# TX.net
KiCad netlist of a schematic drawn in Altium Designer
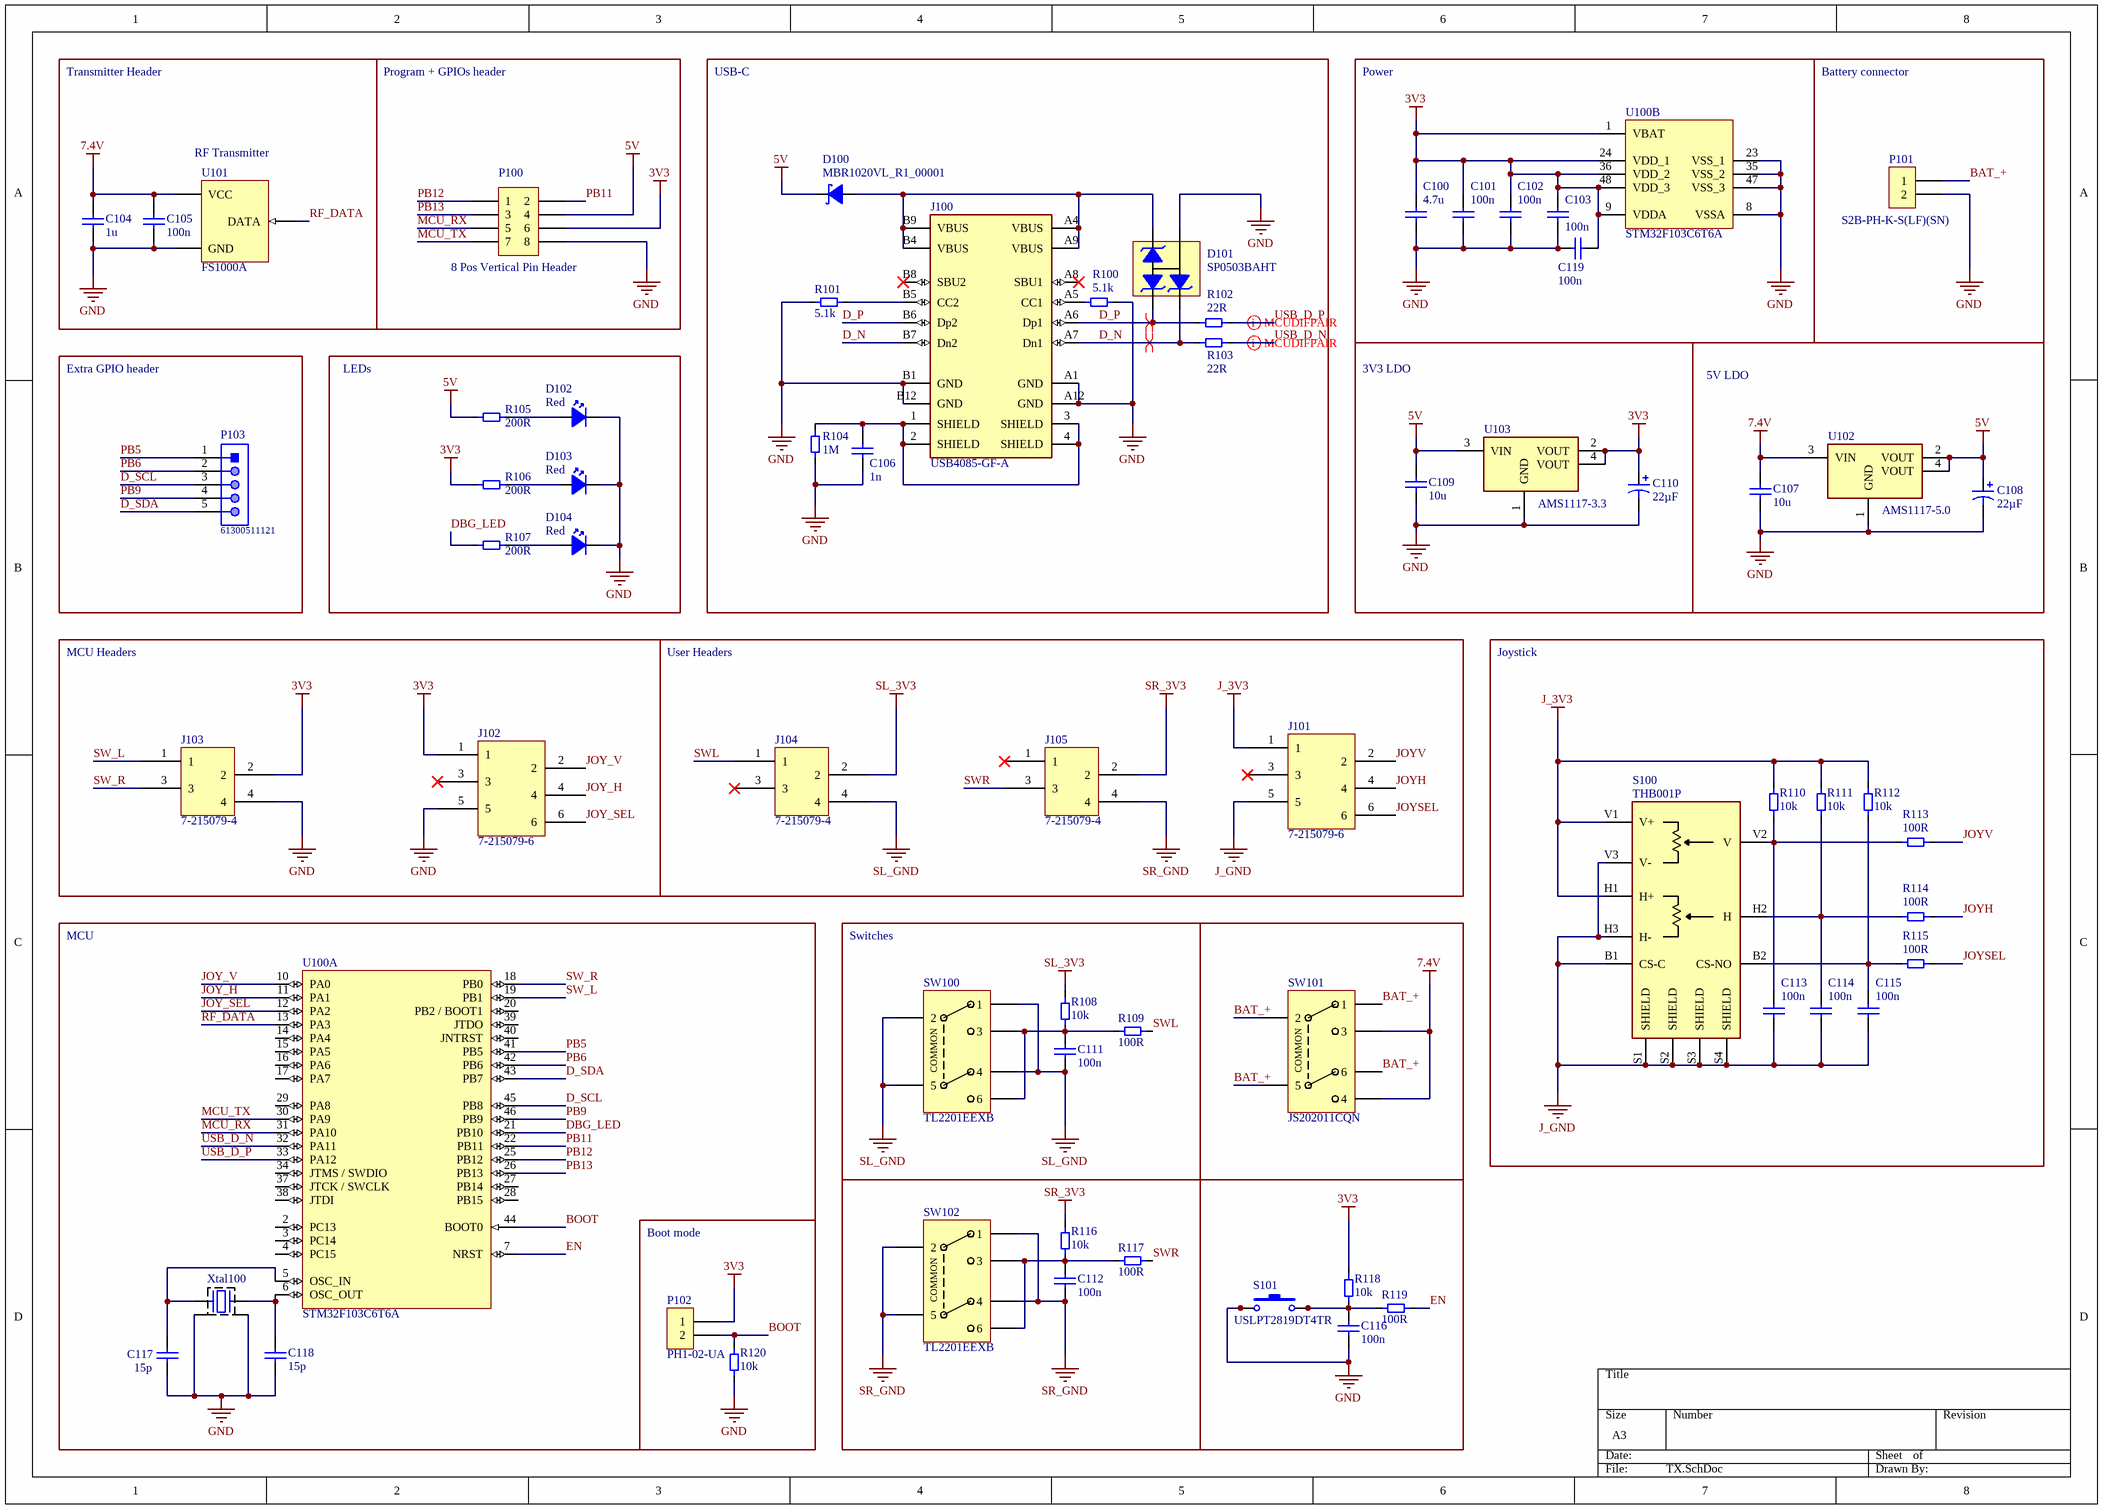
[diagram p0: TX.SchDoc]

(export (version "E")
  (design (tool "Eeschema 10.0.6"))
  (components
    (comp (ref "C100")
      (value "4.7u")
      (footprint "MLCC_0805_M")
      (description "MLCC, 0805, 4.7u, 20%, 50V, X5R")
      (fields (field (name "MANUFACTURER") "Any") (field (name "VOLTAGE") "50V"))
      (libsource (lib "Krakul Vault") (part "CAPACITOR_NONPOL_IEC"))
    )
    (comp (ref "C101")
      (value "100n")
      (footprint "MLCC_0603_M")
      (description "MLCC, 0603, 100n, 10%, 50V, X7R")
      (fields (field (name "VOLTAGE") "50V") (field (name "TOLERANCE") "10%"))
      (libsource (lib "Krakul Vault") (part "CAPACITOR_NONPOL_IEC"))
    )
    (comp (ref "C102")
      (value "100n")
      (footprint "MLCC_0603_M")
      (description "MLCC, 0603, 100n, 10%, 50V, X7R")
      (fields (field (name "VOLTAGE") "50V") (field (name "TOLERANCE") "10%"))
      (libsource (lib "Krakul Vault") (part "CAPACITOR_NONPOL_IEC"))
    )
    (comp (ref "C103")
      (value "100n")
      (footprint "MLCC_0603_M")
      (description "MLCC, 0603, 100n, 10%, 50V, X7R")
      (fields (field (name "VOLTAGE") "50V") (field (name "TOLERANCE") "10%"))
      (libsource (lib "Krakul Vault") (part "CAPACITOR_NONPOL_IEC"))
    )
    (comp (ref "C104")
      (value "1u")
      (footprint "MLCC_0603_M")
      (description "MLCC, 0603, 1u, 10%, 50V, X5R")
      (fields (field (name "MANUFACTURER") "Any") (field (name "VOLTAGE") "50V"))
      (libsource (lib "Krakul Vault") (part "CAPACITOR_NONPOL_IEC"))
    )
    (comp (ref "C105")
      (value "100n")
      (footprint "MLCC_0603_M")
      (description "MLCC, 0603, 100n, 10%, 50V, X7R")
      (fields (field (name "VOLTAGE") "50V") (field (name "TOLERANCE") "10%"))
      (libsource (lib "Krakul Vault") (part "CAPACITOR_NONPOL_IEC"))
    )
    (comp (ref "C106")
      (value "1n")
      (footprint "MLCC_0603_M")
      (description "MLCC, 0603, 1n, 10%, 50V, X7R")
      (fields (field (name "MANUFACTURER") "Any") (field (name "VOLTAGE") "50V"))
      (libsource (lib "Krakul Vault") (part "CAPACITOR_NONPOL_IEC"))
    )
    (comp (ref "C107")
      (value "10u")
      (footprint "MLCC_0805_M")
      (description "MLCC, 0805, 10u, 10%, 50V, X5R")
      (fields (field (name "TOLERANCE") "10%") (field (name "VOLTAGE") "50V"))
      (libsource (lib "Krakul Vault") (part "CAPACITOR_NONPOL_IEC"))
    )
    (comp (ref "C108")
      (value "22µF")
      (footprint "1210_Tantalum")
      (description "Cap Tant Solid 22uF 25V B CASE 20% (3.5 X 2.8 X 1.9mm) SMD 3528-21 0.15 Ohm 105°C T/R")
      (fields (field (name "TOLERANCE") "20%") (field (name "MANUFACTURER") "AVX Corporation"))
      (libsource (lib "Krakul Vault") (part "GENERIC TANT CAP"))
    )
    (comp (ref "C109")
      (value "10u")
      (footprint "MLCC_0805_M")
      (description "MLCC, 0805, 10u, 10%, 50V, X5R")
      (fields (field (name "TOLERANCE") "10%") (field (name "VOLTAGE") "50V"))
      (libsource (lib "Krakul Vault") (part "CAPACITOR_NONPOL_IEC"))
    )
    (comp (ref "C110")
      (value "22µF")
      (footprint "1210_Tantalum")
      (description "Cap Tant Solid 22uF 25V B CASE 20% (3.5 X 2.8 X 1.9mm) SMD 3528-21 0.15 Ohm 105°C T/R")
      (fields (field (name "TOLERANCE") "20%") (field (name "MANUFACTURER") "AVX Corporation"))
      (libsource (lib "Krakul Vault") (part "GENERIC TANT CAP"))
    )
    (comp (ref "C111")
      (value "100n")
      (footprint "MLCC_0603_M")
      (description "MLCC, 0603, 100n, 10%, 50V, X7R")
      (fields (field (name "VOLTAGE") "50V") (field (name "TOLERANCE") "10%"))
      (libsource (lib "Krakul Vault") (part "CAPACITOR_NONPOL_IEC"))
    )
    (comp (ref "C112")
      (value "100n")
      (footprint "MLCC_0603_M")
      (description "MLCC, 0603, 100n, 10%, 50V, X7R")
      (fields (field (name "VOLTAGE") "50V") (field (name "TOLERANCE") "10%"))
      (libsource (lib "Krakul Vault") (part "CAPACITOR_NONPOL_IEC"))
    )
    (comp (ref "C113")
      (value "100n")
      (footprint "MLCC_0603_M")
      (description "MLCC, 0603, 100n, 10%, 50V, X7R")
      (fields (field (name "VOLTAGE") "50V") (field (name "TOLERANCE") "10%"))
      (libsource (lib "Krakul Vault") (part "CAPACITOR_NONPOL_IEC"))
    )
    (comp (ref "C114")
      (value "100n")
      (footprint "MLCC_0603_M")
      (description "MLCC, 0603, 100n, 10%, 50V, X7R")
      (fields (field (name "VOLTAGE") "50V") (field (name "TOLERANCE") "10%"))
      (libsource (lib "Krakul Vault") (part "CAPACITOR_NONPOL_IEC"))
    )
    (comp (ref "C115")
      (value "100n")
      (footprint "MLCC_0603_M")
      (description "MLCC, 0603, 100n, 10%, 50V, X7R")
      (fields (field (name "VOLTAGE") "50V") (field (name "TOLERANCE") "10%"))
      (libsource (lib "Krakul Vault") (part "CAPACITOR_NONPOL_IEC"))
    )
    (comp (ref "C116")
      (value "100n")
      (footprint "MLCC_0603_M")
      (description "MLCC, 0603, 100n, 10%, 50V, X7R")
      (fields (field (name "VOLTAGE") "50V") (field (name "TOLERANCE") "10%"))
      (libsource (lib "Krakul Vault") (part "CAPACITOR_NONPOL_IEC"))
    )
    (comp (ref "C117")
      (value "15p")
      (footprint "MLCC_0402_M")
      (description "MLCC, 0402, 15p, 10%, 25V, C0G/NP0")
      (fields (field (name "MANUFACTURER") "Any") (field (name "TOLERANCE") "10%"))
      (libsource (lib "Krakul Vault") (part "CAPACITOR_NONPOL_IEC"))
    )
    (comp (ref "C118")
      (value "15p")
      (footprint "MLCC_0402_M")
      (description "MLCC, 0402, 15p, 10%, 25V, C0G/NP0")
      (fields (field (name "MANUFACTURER") "Any") (field (name "TOLERANCE") "10%"))
      (libsource (lib "Krakul Vault") (part "CAPACITOR_NONPOL_IEC"))
    )
    (comp (ref "C119")
      (value "100n")
      (footprint "MLCC_0603_M")
      (description "MLCC, 0603, 100n, 10%, 50V, X7R")
      (fields (field (name "VOLTAGE") "50V") (field (name "TOLERANCE") "10%"))
      (libsource (lib "Krakul Vault") (part "CAPACITOR_NONPOL_IEC"))
    )
    (comp (ref "D100")
      (value "MBR1020VL_R1_00001")
      (footprint "FP-MBR1020VL_R1_00001-MFG")
      (description "Rectifier Diode, Schottky, 1 Phase, 1 Element, 1A, 20V V(RRM), Silicon")
      (fields (field (name "MANUFACTURER") "Panjit"))
      (libsource (lib "Krakul Vault") (part "Schottky generic 2 pins"))
    )
    (comp (ref "D101")
      (value "SP0503BAHT")
      (footprint "LFUS-SOT143-4_V")
      (description "SP050xBA Series 8.5 V 30 pF Triple Uni-Directional TVS Avalanche Diode-SOT143-4")
      (fields (field (name "MANUFACTURER") "Littelfuse Inc."))
      (libsource (lib "Krakul Vault") (part "SOT-143"))
    )
    (comp (ref "D102")
      (value "Red")
      (footprint "0603 RED LED")
      (description "Generic red 0603 LED")
      (fields (field (name "PART NUMBER") "Any Red 0603 LED") (field (name "MANUFACTURER") "Any"))
      (libsource (lib "Krakul Vault") (part "LED generic"))
    )
    (comp (ref "D103")
      (value "Red")
      (footprint "0603 RED LED")
      (description "Generic red 0603 LED")
      (fields (field (name "PART NUMBER") "Any Red 0603 LED") (field (name "MANUFACTURER") "Any"))
      (libsource (lib "Krakul Vault") (part "LED generic"))
    )
    (comp (ref "D104")
      (value "Red")
      (footprint "0603 RED LED")
      (description "Generic red 0603 LED")
      (fields (field (name "PART NUMBER") "Any Red 0603 LED") (field (name "MANUFACTURER") "Any"))
      (libsource (lib "Krakul Vault") (part "LED generic"))
    )
    (comp (ref "J100")
      (value "USB4085-GF-A")
      (footprint "FP-USB4085-GF-A-MFG")
      (description "USB Connector, 16 Contact(s), Female, Right Angle, Solder Terminal, Locking, Receptacle")
      (fields (field (name "MANUFACTURER") "GCT") (field (name "PART NUMBER") "USB4800-03-A"))
      (libsource (lib "Krakul Vault") (part "USB4085-GF-A"))
    )
    (comp (ref "J101")
      (value "7-215079-6")
      (footprint "7-215079-6-Footprint-1")
      (description "Conn FFC Connector F 6 POS 1.27mm Solder ST Thru-Hole Automotive Box/Carton")
      (fields (field (name "MANUFACTURER") "TE Connectivity"))
      (libsource (lib "Krakul Vault") (part "7-215079-6"))
    )
    (comp (ref "J102")
      (value "7-215079-6")
      (footprint "7-215079-6-Footprint-1")
      (description "Conn FFC Connector F 6 POS 1.27mm Solder ST Thru-Hole Automotive Box/Carton")
      (fields (field (name "MANUFACTURER") "TE Connectivity"))
      (libsource (lib "Krakul Vault") (part "7-215079-6"))
    )
    (comp (ref "J103")
      (value "7-215079-4")
      (footprint "7-215079-4")
      (description "Conn FFC Connector F 4 POS 1.27mm Solder ST Thru-Hole Box/Carton")
      (fields (field (name "MANUFACTURER") "TE connectivity") (field (name "PART NUMBER") "7-215079-6"))
      (libsource (lib "Krakul Vault") (part "7-215079-4"))
    )
    (comp (ref "J104")
      (value "7-215079-4")
      (footprint "7-215079-4")
      (description "Conn FFC Connector F 4 POS 1.27mm Solder ST Thru-Hole Box/Carton")
      (fields (field (name "MANUFACTURER") "TE connectivity") (field (name "PART NUMBER") "7-215079-6"))
      (libsource (lib "Krakul Vault") (part "7-215079-4"))
    )
    (comp (ref "J105")
      (value "7-215079-4")
      (footprint "7-215079-4")
      (description "Conn FFC Connector F 4 POS 1.27mm Solder ST Thru-Hole Box/Carton")
      (fields (field (name "MANUFACTURER") "TE connectivity") (field (name "PART NUMBER") "7-215079-6"))
      (libsource (lib "Krakul Vault") (part "7-215079-4"))
    )
    (comp (ref "P100")
      (value "8 Pos Vertical Pin Header")
      (footprint "8 POS Vertical Pin Header")
      (description "Connector Header Through Hole 8 position 0.100\" (2.54mm)")
      (fields (field (name "MANUFACTURER") "Amphenol ICC (FCI)") (field (name "PART NUMBER") "67997-208HLF"))
      (libsource (lib "Krakul Vault") (part "8POS GENERIC 2-LINE"))
    )
    (comp (ref "P101")
      (value "S2B-PH-K-S(LF)(SN)")
      (footprint "B5B-PH-K-S(LF)(SN)")
      (description "Conn Shrouded Header (4 Sides) HDR 2 POS 2mm Solder RA Thru-Hole Box")
      (fields (field (name "MANUFACTURER") "JST Sales America Inc."))
      (libsource (lib "Krakul Vault") (part "2POS GENERIC"))
    )
    (comp (ref "P102")
      (value "PH1-02-UA")
      (footprint "2Pos Pin Header Vertical")
      (description "Conn Unshrouded Header HDR 2 POS 2.54mm Solder ST Top Entry Thru-Hole Bag")
      (fields (field (name "PART NUMBER") "PH1-04-UA") (field (name "MANUFACTURER") "Adam Tech"))
      (libsource (lib "Krakul Vault") (part "2POS GENERIC"))
    )
    (comp (ref "P103")
      (value "61300511121")
      (footprint "61300511121")
      (description "Conn Unshrouded Header HDR 5 POS 2.54mm Solder ST Top Entry Thru-Hole Bag")
      (fields (field (name "MANUFACTURER") "Wurth"))
      (libsource (lib "Krakul Vault") (part "WE-CN-1P-M-R5"))
    )
    (comp (ref "R100")
      (value "5.1k")
      (footprint "Resistor_0603_M")
      (description "Resistor, 0603, 5.1k, 1%, 1/10W")
      (fields (field (name "POWER") "100mW") (field (name "MANUFACTURER") "Any"))
      (libsource (lib "Krakul Vault") (part "RESISTOR_GENERIC_IEC"))
    )
    (comp (ref "R101")
      (value "5.1k")
      (footprint "Resistor_0603_M")
      (description "Resistor, 0603, 5.1k, 1%, 1/10W")
      (fields (field (name "POWER") "100mW") (field (name "MANUFACTURER") "Any"))
      (libsource (lib "Krakul Vault") (part "RESISTOR_GENERIC_IEC"))
    )
    (comp (ref "R102")
      (value "22R")
      (footprint "Resistor_0603_M")
      (description "Resistor, 0603, 22R, 1%, 1/10W")
      (fields (field (name "TOLERANCE") "1%") (field (name "MANUFACTURER") "Any"))
      (libsource (lib "Krakul Vault") (part "RESISTOR_GENERIC_IEC"))
    )
    (comp (ref "R103")
      (value "22R")
      (footprint "Resistor_0603_M")
      (description "Resistor, 0603, 22R, 1%, 1/10W")
      (fields (field (name "TOLERANCE") "1%") (field (name "MANUFACTURER") "Any"))
      (libsource (lib "Krakul Vault") (part "RESISTOR_GENERIC_IEC"))
    )
    (comp (ref "R104")
      (value "1M")
      (footprint "Resistor_1206_M")
      (description "Resistor, 1206, 1M, 1%, 1/4W")
      (fields (field (name "MANUFACTURER") "Any"))
      (libsource (lib "Krakul Vault") (part "RESISTOR_GENERIC_IEC"))
    )
    (comp (ref "R105")
      (value "200R")
      (footprint "Resistor_0603_M")
      (description "Resistor, 0603, 200R, 1%, 1/10W")
      (fields (field (name "TOLERANCE") "1%") (field (name "POWER") "100mW"))
      (libsource (lib "Krakul Vault") (part "RESISTOR_GENERIC_IEC"))
    )
    (comp (ref "R106")
      (value "200R")
      (footprint "Resistor_0603_M")
      (description "Resistor, 0603, 200R, 1%, 1/10W")
      (fields (field (name "TOLERANCE") "1%") (field (name "POWER") "100mW"))
      (libsource (lib "Krakul Vault") (part "RESISTOR_GENERIC_IEC"))
    )
    (comp (ref "R107")
      (value "200R")
      (footprint "Resistor_0603_M")
      (description "Resistor, 0603, 200R, 1%, 1/10W")
      (fields (field (name "TOLERANCE") "1%") (field (name "POWER") "100mW"))
      (libsource (lib "Krakul Vault") (part "RESISTOR_GENERIC_IEC"))
    )
    (comp (ref "R108")
      (value "10k")
      (footprint "Resistor_0603_M")
      (description "Resistor, 0603, 10k, 1%, 1/10W")
      (fields (field (name "MANUFACTURER") "Any") (field (name "TOLERANCE") "1%"))
      (libsource (lib "Krakul Vault") (part "RESISTOR_GENERIC_IEC"))
    )
    (comp (ref "R109")
      (value "100R")
      (footprint "Resistor_0603_M")
      (description "Resistor, 0603, 100R, 1%, 1/10W")
      (fields (field (name "POWER") "100mW") (field (name "MANUFACTURER") "Any"))
      (libsource (lib "Krakul Vault") (part "RESISTOR_GENERIC_IEC"))
    )
    (comp (ref "R110")
      (value "10k")
      (footprint "Resistor_0603_M")
      (description "Resistor, 0603, 10k, 1%, 1/10W")
      (fields (field (name "MANUFACTURER") "Any") (field (name "TOLERANCE") "1%"))
      (libsource (lib "Krakul Vault") (part "RESISTOR_GENERIC_IEC"))
    )
    (comp (ref "R111")
      (value "10k")
      (footprint "Resistor_0603_M")
      (description "Resistor, 0603, 10k, 1%, 1/10W")
      (fields (field (name "MANUFACTURER") "Any") (field (name "TOLERANCE") "1%"))
      (libsource (lib "Krakul Vault") (part "RESISTOR_GENERIC_IEC"))
    )
    (comp (ref "R112")
      (value "10k")
      (footprint "Resistor_0603_M")
      (description "Resistor, 0603, 10k, 1%, 1/10W")
      (fields (field (name "MANUFACTURER") "Any") (field (name "TOLERANCE") "1%"))
      (libsource (lib "Krakul Vault") (part "RESISTOR_GENERIC_IEC"))
    )
    (comp (ref "R113")
      (value "100R")
      (footprint "Resistor_0603_M")
      (description "Resistor, 0603, 100R, 1%, 1/10W")
      (fields (field (name "POWER") "100mW") (field (name "MANUFACTURER") "Any"))
      (libsource (lib "Krakul Vault") (part "RESISTOR_GENERIC_IEC"))
    )
    (comp (ref "R114")
      (value "100R")
      (footprint "Resistor_0603_M")
      (description "Resistor, 0603, 100R, 1%, 1/10W")
      (fields (field (name "POWER") "100mW") (field (name "MANUFACTURER") "Any"))
      (libsource (lib "Krakul Vault") (part "RESISTOR_GENERIC_IEC"))
    )
    (comp (ref "R115")
      (value "100R")
      (footprint "Resistor_0603_M")
      (description "Resistor, 0603, 100R, 1%, 1/10W")
      (fields (field (name "POWER") "100mW") (field (name "MANUFACTURER") "Any"))
      (libsource (lib "Krakul Vault") (part "RESISTOR_GENERIC_IEC"))
    )
    (comp (ref "R116")
      (value "10k")
      (footprint "Resistor_0603_M")
      (description "Resistor, 0603, 10k, 1%, 1/10W")
      (fields (field (name "MANUFACTURER") "Any") (field (name "TOLERANCE") "1%"))
      (libsource (lib "Krakul Vault") (part "RESISTOR_GENERIC_IEC"))
    )
    (comp (ref "R117")
      (value "100R")
      (footprint "Resistor_0603_M")
      (description "Resistor, 0603, 100R, 1%, 1/10W")
      (fields (field (name "POWER") "100mW") (field (name "MANUFACTURER") "Any"))
      (libsource (lib "Krakul Vault") (part "RESISTOR_GENERIC_IEC"))
    )
    (comp (ref "R118")
      (value "10k")
      (footprint "Resistor_0603_M")
      (description "Resistor, 0603, 10k, 1%, 1/10W")
      (fields (field (name "MANUFACTURER") "Any") (field (name "TOLERANCE") "1%"))
      (libsource (lib "Krakul Vault") (part "RESISTOR_GENERIC_IEC"))
    )
    (comp (ref "R119")
      (value "100R")
      (footprint "Resistor_0603_M")
      (description "Resistor, 0603, 100R, 1%, 1/10W")
      (fields (field (name "POWER") "100mW") (field (name "MANUFACTURER") "Any"))
      (libsource (lib "Krakul Vault") (part "RESISTOR_GENERIC_IEC"))
    )
    (comp (ref "R120")
      (value "10k")
      (footprint "Resistor_0603_M")
      (description "Resistor, 0603, 10k, ≤5%, ≥1/16W")
      (fields (field (name "MANUFACTURER") "Any"))
      (libsource (lib "Krakul Vault") (part "RESISTOR_GENERIC_IEC"))
    )
    (comp (ref "S100")
      (value "THB001P")
      (footprint "THB001P")
      (description "Multi-Directional Thumbstick, 2 Axis, Center Momentary Switch, 12VDC, THB Series")
      (fields (field (name "MANUFACTURER") "Littelfuse"))
      (libsource (lib "Krakul Vault") (part "THB001P"))
    )
    (comp (ref "S101")
      (value "USLPT2819DT4TR")
      (footprint "USLPT2819DT4TR-Footprint-1")
      (description "Keypad Switch, SPST, 0.05A, 1.96N, Solder Terminal, Panel Mount")
      (fields (field (name "MANUFACTURER") "TE Connectivity ALCOSWITCH Switches"))
      (libsource (lib "Krakul Vault") (part "Copy of Switch 4-pin"))
    )
    (comp (ref "SW100")
      (value "TL2201EEXB")
      (footprint "TL2201EEXB-Footprint-1")
      (description "Pushbutton Switch, DPDT, ON-ON, 100 mA, 30V DC, PC Pin, TL2201 Series")
      (fields (field (name "MANUFACTURER") "E-Switch"))
      (libsource (lib "Krakul Vault") (part "TL2201EEXB-Symbol-1"))
    )
    (comp (ref "SW101")
      (value "JS202011CQN")
      (footprint "FP-JS202011CQN-MFG")
      (description "Slide Switch, 1 Positions, Dpdt, Latched, 0.3A, 6Vdc, 6 Pcb Hole Cnt, Solder Terminal, Through")
      (fields (field (name "MANUFACTURER") "C&K"))
      (libsource (lib "Krakul Vault") (part "JS202011CQN-Symbol-1"))
    )
    (comp (ref "SW102")
      (value "TL2201EEXB")
      (footprint "TL2201EEXB-Footprint-1")
      (description "Pushbutton Switch, DPDT, ON-ON, 100 mA, 30V DC, PC Pin, TL2201 Series")
      (fields (field (name "MANUFACTURER") "E-Switch"))
      (libsource (lib "Krakul Vault") (part "TL2201EEXB-Symbol-1"))
    )
    (comp (ref "U100")
      (value "STM32F103C6T6A")
      (footprint "STM-LQFP48_M")
      (description "MCU 32-bit STM32F ARM Cortex M3 RISC 32KB Flash 2.5V/3.3V 48-Pin LQFP Tray")
      (fields (field (name "MANUFACTURER") "STMicroelectronics") (field (name "PART NUMBER") "STM32F103C8T6"))
      (libsource (lib "Krakul Vault") (part "MC-ARM-STM32F103X4_6-SQ48"))
    )
    (comp (ref "U101")
      (value "FS1000A")
      (footprint "2.54mm 3-pin horizontal")
      (description "FS1000A 433MHZ RF transmitter & XY-MK-5V Receiver Module")
      (libsource (lib "Krakul Vault") (part "FS1000A"))
    )
    (comp (ref "U102")
      (value "AMS1117-5.0")
      (footprint "SOT230P700X180-4N")
      (description "LDO Regulator Pos 5V 1A 4-Pin(3+Tab) SOT-223 / 1A LOW DROPOUT VOLTAGE REGULATOR")
      (fields (field (name "MANUFACTURER") "EVVO"))
      (libsource (lib "Krakul Vault") (part "AMS1117-3.3"))
    )
    (comp (ref "U103")
      (value "AMS1117-3.3")
      (footprint "SOT-223 based on ZVP2110GTA")
      (fields (field (name "MANUFACTURER") "Shenzhen Slkormicro Semicon Co., Ltd."))
      (libsource (lib "Krakul Vault") (part "AMS1117-3.3"))
    )
    (comp (ref "Xtal100")
      (value "ABM11-16.000MHZ-12-N1G-T")
      (footprint "FP-ABM11-MFG")
      (description "Crystal 16MHz ±10ppm (Tol) ±15ppm (Stability) 12pF FUND 150Ohm 4-Pin Ultra Mini-CSMD T/R")
      (fields (field (name "MANUFACTURER") "Abracon LLC") (field (name "TOLERANCE") "0.001%"))
      (libsource (lib "Krakul Vault") (part "Crystal 4 pins"))
    )
  )
  (nets
    (net (code "1") (name "/BAT_+") (class "Default")
      (node (ref "P101") (pin "1") (pinfunction "1_1") (pintype "passive"))
      (node (ref "SW101") (pin "1") (pinfunction "1_1") (pintype "passive"))
      (node (ref "SW101") (pin "2") (pinfunction "2_2") (pintype "passive"))
      (node (ref "SW101") (pin "5") (pinfunction "5_5") (pintype "passive"))
      (node (ref "SW101") (pin "6") (pinfunction "6_6") (pintype "passive"))
    )
    (net (code "2") (name "/BOOT") (class "Default")
      (node (ref "P102") (pin "2") (pinfunction "2_2") (pintype "passive"))
      (node (ref "R120") (pin "2") (pinfunction "2_2") (pintype "passive"))
      (node (ref "U100") (pin "44") (pinfunction "BOOT0_44") (pintype "input"))
    )
    (net (code "3") (name "/DBG_LED") (class "Default")
      (node (ref "R107") (pin "1") (pinfunction "1_1") (pintype "passive"))
      (node (ref "U100") (pin "21") (pinfunction "PB10_21") (pintype "bidirectional"))
    )
    (net (code "4") (name "/D_N") (class "Default")
      (node (ref "D101") (pin "4") (pinfunction "C_4") (pintype "passive"))
      (node (ref "J100") (pin "A7") (pinfunction "Dn1_A7") (pintype "bidirectional"))
      (node (ref "J100") (pin "B7") (pinfunction "Dn2_B7") (pintype "bidirectional"))
      (node (ref "R103") (pin "1") (pinfunction "1_1") (pintype "passive"))
    )
    (net (code "5") (name "/D_P") (class "Default")
      (node (ref "D101") (pin "3") (pinfunction "C_3") (pintype "passive"))
      (node (ref "J100") (pin "A6") (pinfunction "Dp1_A6") (pintype "bidirectional"))
      (node (ref "J100") (pin "B6") (pinfunction "Dp2_B6") (pintype "bidirectional"))
      (node (ref "R102") (pin "1") (pinfunction "1_1") (pintype "passive"))
    )
    (net (code "6") (name "/D_SCL") (class "Default")
      (node (ref "P103") (pin "3") (pinfunction "3_3") (pintype "passive"))
      (node (ref "U100") (pin "45") (pinfunction "PB8_45") (pintype "bidirectional"))
    )
    (net (code "7") (name "/D_SDA") (class "Default")
      (node (ref "P103") (pin "5") (pinfunction "5_5") (pintype "passive"))
      (node (ref "U100") (pin "43") (pinfunction "PB7_43") (pintype "bidirectional"))
    )
    (net (code "8") (name "/EN") (class "Default")
      (node (ref "R119") (pin "2") (pinfunction "2_2") (pintype "passive"))
      (node (ref "U100") (pin "7") (pinfunction "NRST_7") (pintype "bidirectional"))
    )
    (net (code "9") (name "/JOYH") (class "Default")
      (node (ref "J101") (pin "4") (pinfunction "4_4") (pintype "passive"))
      (node (ref "R114") (pin "2") (pinfunction "2_2") (pintype "passive"))
    )
    (net (code "10") (name "/JOYSEL") (class "Default")
      (node (ref "J101") (pin "6") (pinfunction "6_6") (pintype "passive"))
      (node (ref "R115") (pin "2") (pinfunction "2_2") (pintype "passive"))
    )
    (net (code "11") (name "/JOYV") (class "Default")
      (node (ref "J101") (pin "2") (pinfunction "2_2") (pintype "passive"))
      (node (ref "R113") (pin "2") (pinfunction "2_2") (pintype "passive"))
    )
    (net (code "12") (name "/JOY_H") (class "Default")
      (node (ref "J102") (pin "4") (pinfunction "4_4") (pintype "passive"))
      (node (ref "U100") (pin "11") (pinfunction "PA1_11") (pintype "bidirectional"))
    )
    (net (code "13") (name "/JOY_SEL") (class "Default")
      (node (ref "J102") (pin "6") (pinfunction "6_6") (pintype "passive"))
      (node (ref "U100") (pin "12") (pinfunction "PA2_12") (pintype "bidirectional"))
    )
    (net (code "14") (name "/JOY_V") (class "Default")
      (node (ref "J102") (pin "2") (pinfunction "2_2") (pintype "passive"))
      (node (ref "U100") (pin "10") (pinfunction "PA0_10") (pintype "bidirectional"))
    )
    (net (code "15") (name "/MCU_RX") (class "Default")
      (node (ref "P100") (pin "5") (pinfunction "5_5") (pintype "passive"))
      (node (ref "U100") (pin "31") (pinfunction "PA10_31") (pintype "bidirectional"))
    )
    (net (code "16") (name "/MCU_TX") (class "Default")
      (node (ref "P100") (pin "7") (pinfunction "7_7") (pintype "passive"))
      (node (ref "U100") (pin "30") (pinfunction "PA9_30") (pintype "bidirectional"))
    )
    (net (code "17") (name "/PB5") (class "Default")
      (node (ref "P103") (pin "1") (pinfunction "1_1") (pintype "passive"))
      (node (ref "U100") (pin "41") (pinfunction "PB5_41") (pintype "bidirectional"))
    )
    (net (code "18") (name "/PB6") (class "Default")
      (node (ref "P103") (pin "2") (pinfunction "2_2") (pintype "passive"))
      (node (ref "U100") (pin "42") (pinfunction "PB6_42") (pintype "bidirectional"))
    )
    (net (code "19") (name "/PB9") (class "Default")
      (node (ref "P103") (pin "4") (pinfunction "4_4") (pintype "passive"))
      (node (ref "U100") (pin "46") (pinfunction "PB9_46") (pintype "bidirectional"))
    )
    (net (code "20") (name "/PB11") (class "Default")
      (node (ref "P100") (pin "2") (pinfunction "2_2") (pintype "passive"))
      (node (ref "U100") (pin "22") (pinfunction "PB11_22") (pintype "bidirectional"))
    )
    (net (code "21") (name "/PB12") (class "Default")
      (node (ref "P100") (pin "1") (pinfunction "1_1") (pintype "passive"))
      (node (ref "U100") (pin "25") (pinfunction "PB12_25") (pintype "bidirectional"))
    )
    (net (code "22") (name "/PB13") (class "Default")
      (node (ref "P100") (pin "3") (pinfunction "3_3") (pintype "passive"))
      (node (ref "U100") (pin "26") (pinfunction "PB13_26") (pintype "bidirectional"))
    )
    (net (code "23") (name "/RF_DATA") (class "Default")
      (node (ref "U100") (pin "13") (pinfunction "PA3_13") (pintype "bidirectional"))
      (node (ref "U101") (pin "3") (pinfunction "DATA_3") (pintype "input"))
    )
    (net (code "24") (name "/SWL") (class "Default")
      (node (ref "J104") (pin "1") (pinfunction "1_1") (pintype "passive"))
      (node (ref "R109") (pin "2") (pinfunction "2_2") (pintype "passive"))
    )
    (net (code "25") (name "/SWR") (class "Default")
      (node (ref "J105") (pin "3") (pinfunction "3_3") (pintype "passive"))
      (node (ref "R117") (pin "2") (pinfunction "2_2") (pintype "passive"))
    )
    (net (code "26") (name "/SW_L") (class "Default")
      (node (ref "J103") (pin "1") (pinfunction "1_1") (pintype "passive"))
      (node (ref "U100") (pin "19") (pinfunction "PB1_19") (pintype "bidirectional"))
    )
    (net (code "27") (name "/SW_R") (class "Default")
      (node (ref "J103") (pin "3") (pinfunction "3_3") (pintype "passive"))
      (node (ref "U100") (pin "18") (pinfunction "PB0_18") (pintype "bidirectional"))
    )
    (net (code "28") (name "/USB_D_N") (class "Default")
      (node (ref "R103") (pin "2") (pinfunction "2_2") (pintype "passive"))
      (node (ref "U100") (pin "32") (pinfunction "PA11_32") (pintype "bidirectional"))
    )
    (net (code "29") (name "/USB_D_P") (class "Default")
      (node (ref "R102") (pin "2") (pinfunction "2_2") (pintype "passive"))
      (node (ref "U100") (pin "33") (pinfunction "PA12_33") (pintype "bidirectional"))
    )
    (net (code "30") (name "3V3") (class "Default")
      (node (ref "C100") (pin "2") (pinfunction "2_2") (pintype "passive"))
      (node (ref "C101") (pin "1") (pinfunction "1_1") (pintype "passive"))
      (node (ref "C102") (pin "1") (pinfunction "1_1") (pintype "passive"))
      (node (ref "C103") (pin "1") (pinfunction "1_1") (pintype "passive"))
      (node (ref "C110") (pin "1") (pinfunction "1_1") (pintype "passive"))
      (node (ref "C119") (pin "2") (pinfunction "2_2") (pintype "passive"))
      (node (ref "J102") (pin "1") (pinfunction "1_1") (pintype "passive"))
      (node (ref "J103") (pin "2") (pinfunction "2_2") (pintype "passive"))
      (node (ref "P100") (pin "6") (pinfunction "6_6") (pintype "passive"))
      (node (ref "P102") (pin "1") (pinfunction "1_1") (pintype "passive"))
      (node (ref "R106") (pin "1") (pinfunction "1_1") (pintype "passive"))
      (node (ref "R118") (pin "2") (pinfunction "2_2") (pintype "passive"))
      (node (ref "U100") (pin "1") (pinfunction "VBAT_1") (pintype "power_in"))
      (node (ref "U100") (pin "24") (pinfunction "VDD_1_24") (pintype "power_in"))
      (node (ref "U100") (pin "36") (pinfunction "VDD_2_36") (pintype "power_in"))
      (node (ref "U100") (pin "48") (pinfunction "VDD_3_48") (pintype "power_in"))
      (node (ref "U100") (pin "9") (pinfunction "VDDA_9") (pintype "power_in"))
      (node (ref "U103") (pin "2") (pinfunction "VOUT_2") (pintype "passive"))
      (node (ref "U103") (pin "4") (pinfunction "VOUT_4") (pintype "passive"))
    )
    (net (code "31") (name "5V") (class "Default")
      (node (ref "C108") (pin "1") (pinfunction "1_1") (pintype "passive"))
      (node (ref "C109") (pin "2") (pinfunction "2_2") (pintype "passive"))
      (node (ref "D100") (pin "1") (pinfunction "C_1") (pintype "passive"))
      (node (ref "P100") (pin "4") (pinfunction "4_4") (pintype "passive"))
      (node (ref "R105") (pin "1") (pinfunction "1_1") (pintype "passive"))
      (node (ref "U102") (pin "2") (pinfunction "VOUT_2") (pintype "passive"))
      (node (ref "U102") (pin "4") (pinfunction "VOUT_4") (pintype "passive"))
      (node (ref "U103") (pin "3") (pinfunction "VIN_3") (pintype "power_in"))
    )
    (net (code "32") (name "7.4V") (class "Default")
      (node (ref "C104") (pin "2") (pinfunction "2_2") (pintype "passive"))
      (node (ref "C105") (pin "2") (pinfunction "2_2") (pintype "passive"))
      (node (ref "C107") (pin "2") (pinfunction "2_2") (pintype "passive"))
      (node (ref "SW101") (pin "3") (pinfunction "3_3") (pintype "passive"))
      (node (ref "SW101") (pin "4") (pinfunction "4_4") (pintype "passive"))
      (node (ref "U101") (pin "2") (pinfunction "VCC_2") (pintype "power_in"))
      (node (ref "U102") (pin "3") (pinfunction "VIN_3") (pintype "power_in"))
    )
    (net (code "33") (name "GND") (class "Default")
      (node (ref "C100") (pin "1") (pinfunction "1_1") (pintype "passive"))
      (node (ref "C101") (pin "2") (pinfunction "2_2") (pintype "passive"))
      (node (ref "C102") (pin "2") (pinfunction "2_2") (pintype "passive"))
      (node (ref "C103") (pin "2") (pinfunction "2_2") (pintype "passive"))
      (node (ref "C104") (pin "1") (pinfunction "1_1") (pintype "passive"))
      (node (ref "C105") (pin "1") (pinfunction "1_1") (pintype "passive"))
      (node (ref "C106") (pin "1") (pinfunction "1_1") (pintype "passive"))
      (node (ref "C107") (pin "1") (pinfunction "1_1") (pintype "passive"))
      (node (ref "C108") (pin "2") (pinfunction "2_2") (pintype "passive"))
      (node (ref "C109") (pin "1") (pinfunction "1_1") (pintype "passive"))
      (node (ref "C110") (pin "2") (pinfunction "2_2") (pintype "passive"))
      (node (ref "C116") (pin "1") (pinfunction "1_1") (pintype "passive"))
      (node (ref "C117") (pin "1") (pinfunction "1_1") (pintype "passive"))
      (node (ref "C118") (pin "1") (pinfunction "1_1") (pintype "passive"))
      (node (ref "C119") (pin "1") (pinfunction "1_1") (pintype "passive"))
      (node (ref "D101") (pin "1") (pinfunction "A_1") (pintype "passive"))
      (node (ref "D102") (pin "1") (pinfunction "C_1") (pintype "passive"))
      (node (ref "D103") (pin "1") (pinfunction "C_1") (pintype "passive"))
      (node (ref "D104") (pin "1") (pinfunction "C_1") (pintype "passive"))
      (node (ref "J100") (pin "A1") (pinfunction "GND_A1") (pintype "power_in"))
      (node (ref "J100") (pin "A12") (pinfunction "GND_A12") (pintype "power_in"))
      (node (ref "J100") (pin "B1") (pinfunction "GND_B1") (pintype "power_in"))
      (node (ref "J100") (pin "B12") (pinfunction "GND_B12") (pintype "power_in"))
      (node (ref "J102") (pin "5") (pinfunction "5_5") (pintype "passive"))
      (node (ref "J103") (pin "4") (pinfunction "4_4") (pintype "passive"))
      (node (ref "P100") (pin "8") (pinfunction "8_8") (pintype "passive"))
      (node (ref "P101") (pin "2") (pinfunction "2_2") (pintype "passive"))
      (node (ref "R100") (pin "2") (pinfunction "2_2") (pintype "passive"))
      (node (ref "R101") (pin "1") (pinfunction "1_1") (pintype "passive"))
      (node (ref "R104") (pin "1") (pinfunction "1_1") (pintype "passive"))
      (node (ref "R120") (pin "1") (pinfunction "1_1") (pintype "passive"))
      (node (ref "S101") (pin "1") (pinfunction "1_1") (pintype "passive"))
      (node (ref "S101") (pin "2") (pinfunction "2_2") (pintype "passive"))
      (node (ref "U100") (pin "23") (pinfunction "VSS_1_23") (pintype "power_in"))
      (node (ref "U100") (pin "35") (pinfunction "VSS_2_35") (pintype "power_in"))
      (node (ref "U100") (pin "47") (pinfunction "VSS_3_47") (pintype "power_in"))
      (node (ref "U100") (pin "8") (pinfunction "VSSA_8") (pintype "power_in"))
      (node (ref "U101") (pin "1") (pinfunction "GND_1") (pintype "power_in"))
      (node (ref "U102") (pin "1") (pinfunction "GND_1") (pintype "power_in"))
      (node (ref "U103") (pin "1") (pinfunction "GND_1") (pintype "power_in"))
      (node (ref "Xtal100") (pin "2") (pinfunction "2_2") (pintype "power_in"))
      (node (ref "Xtal100") (pin "4") (pinfunction "4_4") (pintype "power_in"))
    )
    (net (code "34") (name "J_3V3") (class "Default")
      (node (ref "J101") (pin "1") (pinfunction "1_1") (pintype "passive"))
      (node (ref "R110") (pin "2") (pinfunction "2_2") (pintype "passive"))
      (node (ref "R111") (pin "2") (pinfunction "2_2") (pintype "passive"))
      (node (ref "R112") (pin "2") (pinfunction "2_2") (pintype "passive"))
      (node (ref "S100") (pin "H1") (pinfunction "H+_H1") (pintype "passive"))
      (node (ref "S100") (pin "V1") (pinfunction "V+_V1") (pintype "passive"))
    )
    (net (code "35") (name "J_GND") (class "Default")
      (node (ref "C113") (pin "1") (pinfunction "1_1") (pintype "passive"))
      (node (ref "C114") (pin "1") (pinfunction "1_1") (pintype "passive"))
      (node (ref "C115") (pin "1") (pinfunction "1_1") (pintype "passive"))
      (node (ref "J101") (pin "5") (pinfunction "5_5") (pintype "passive"))
      (node (ref "S100") (pin "B1") (pinfunction "CS-C_B1") (pintype "passive"))
      (node (ref "S100") (pin "H3") (pinfunction "H-_H3") (pintype "passive"))
      (node (ref "S100") (pin "S1") (pinfunction "SHIELD_S1") (pintype "passive"))
      (node (ref "S100") (pin "S2") (pinfunction "SHIELD_S2") (pintype "passive"))
      (node (ref "S100") (pin "S3") (pinfunction "SHIELD_S3") (pintype "passive"))
      (node (ref "S100") (pin "S4") (pinfunction "SHIELD_S4") (pintype "passive"))
      (node (ref "S100") (pin "V3") (pinfunction "V-_V3") (pintype "passive"))
    )
    (net (code "36") (name "Net-(C106-Pad2)") (class "Default")
      (node (ref "C106") (pin "2") (pinfunction "2_2") (pintype "passive"))
      (node (ref "J100") (pin "1") (pinfunction "SHIELD_1") (pintype "passive"))
      (node (ref "J100") (pin "2") (pinfunction "SHIELD_2") (pintype "passive"))
      (node (ref "J100") (pin "3") (pinfunction "SHIELD_3") (pintype "passive"))
      (node (ref "J100") (pin "4") (pinfunction "SHIELD_4") (pintype "passive"))
      (node (ref "R104") (pin "2") (pinfunction "2_2") (pintype "passive"))
    )
    (net (code "37") (name "Net-(C111-Pad2)") (class "Default")
      (node (ref "C111") (pin "2") (pinfunction "2_2") (pintype "passive"))
      (node (ref "R108") (pin "1") (pinfunction "1_1") (pintype "passive"))
      (node (ref "R109") (pin "1") (pinfunction "1_1") (pintype "passive"))
      (node (ref "SW100") (pin "3") (pinfunction "3_3") (pintype "passive"))
      (node (ref "SW100") (pin "6") (pinfunction "6_6") (pintype "passive"))
    )
    (net (code "38") (name "Net-(C112-Pad2)") (class "Default")
      (node (ref "C112") (pin "2") (pinfunction "2_2") (pintype "passive"))
      (node (ref "R116") (pin "1") (pinfunction "1_1") (pintype "passive"))
      (node (ref "R117") (pin "1") (pinfunction "1_1") (pintype "passive"))
      (node (ref "SW102") (pin "3") (pinfunction "3_3") (pintype "passive"))
      (node (ref "SW102") (pin "6") (pinfunction "6_6") (pintype "passive"))
    )
    (net (code "39") (name "Net-(C116-Pad2)") (class "Default")
      (node (ref "C116") (pin "2") (pinfunction "2_2") (pintype "passive"))
      (node (ref "R118") (pin "1") (pinfunction "1_1") (pintype "passive"))
      (node (ref "R119") (pin "1") (pinfunction "1_1") (pintype "passive"))
      (node (ref "S101") (pin "3") (pinfunction "3_3") (pintype "passive"))
      (node (ref "S101") (pin "4") (pinfunction "4_4") (pintype "passive"))
    )
    (net (code "40") (name "Net-(D100-A)") (class "Default")
      (node (ref "D100") (pin "2") (pinfunction "A_2") (pintype "passive"))
      (node (ref "D101") (pin "2") (pinfunction "C_2") (pintype "passive"))
      (node (ref "J100") (pin "A4") (pinfunction "VBUS_A4") (pintype "power_in"))
      (node (ref "J100") (pin "A9") (pinfunction "VBUS_A9") (pintype "power_in"))
      (node (ref "J100") (pin "B4") (pinfunction "VBUS_B4") (pintype "power_in"))
      (node (ref "J100") (pin "B9") (pinfunction "VBUS_B9") (pintype "power_in"))
    )
    (net (code "41") (name "Net-(D102-A)") (class "Default")
      (node (ref "D102") (pin "2") (pinfunction "A_2") (pintype "passive"))
      (node (ref "R105") (pin "2") (pinfunction "2_2") (pintype "passive"))
    )
    (net (code "42") (name "Net-(D103-A)") (class "Default")
      (node (ref "D103") (pin "2") (pinfunction "A_2") (pintype "passive"))
      (node (ref "R106") (pin "2") (pinfunction "2_2") (pintype "passive"))
    )
    (net (code "43") (name "Net-(D104-A)") (class "Default")
      (node (ref "D104") (pin "2") (pinfunction "A_2") (pintype "passive"))
      (node (ref "R107") (pin "2") (pinfunction "2_2") (pintype "passive"))
    )
    (net (code "44") (name "Net-(J100-CC1)") (class "Default")
      (node (ref "J100") (pin "A5") (pinfunction "CC1_A5") (pintype "bidirectional"))
      (node (ref "R100") (pin "1") (pinfunction "1_1") (pintype "passive"))
    )
    (net (code "45") (name "Net-(J100-CC2)") (class "Default")
      (node (ref "J100") (pin "B5") (pinfunction "CC2_B5") (pintype "bidirectional"))
      (node (ref "R101") (pin "2") (pinfunction "2_2") (pintype "passive"))
    )
    (net (code "46") (name "Net-(S100-CS-NO)") (class "Default")
      (node (ref "C115") (pin "2") (pinfunction "2_2") (pintype "passive"))
      (node (ref "R112") (pin "1") (pinfunction "1_1") (pintype "passive"))
      (node (ref "R115") (pin "1") (pinfunction "1_1") (pintype "passive"))
      (node (ref "S100") (pin "B2") (pinfunction "CS-NO_B2") (pintype "passive"))
    )
    (net (code "47") (name "Net-(S100-H)") (class "Default")
      (node (ref "C114") (pin "2") (pinfunction "2_2") (pintype "passive"))
      (node (ref "R111") (pin "1") (pinfunction "1_1") (pintype "passive"))
      (node (ref "R114") (pin "1") (pinfunction "1_1") (pintype "passive"))
      (node (ref "S100") (pin "H2") (pinfunction "H_H2") (pintype "passive"))
    )
    (net (code "48") (name "Net-(S100-V)") (class "Default")
      (node (ref "C113") (pin "2") (pinfunction "2_2") (pintype "passive"))
      (node (ref "R110") (pin "1") (pinfunction "1_1") (pintype "passive"))
      (node (ref "R113") (pin "1") (pinfunction "1_1") (pintype "passive"))
      (node (ref "S100") (pin "V2") (pinfunction "V_V2") (pintype "passive"))
    )
    (net (code "49") (name "Net-(U100A-OSC_IN)") (class "Default")
      (node (ref "C117") (pin "2") (pinfunction "2_2") (pintype "passive"))
      (node (ref "U100") (pin "5") (pinfunction "OSC_IN_5") (pintype "bidirectional"))
      (node (ref "Xtal100") (pin "1") (pinfunction "1_1") (pintype "passive"))
    )
    (net (code "50") (name "Net-(U100A-OSC_OUT)") (class "Default")
      (node (ref "C118") (pin "2") (pinfunction "2_2") (pintype "passive"))
      (node (ref "U100") (pin "6") (pinfunction "OSC_OUT_6") (pintype "bidirectional"))
      (node (ref "Xtal100") (pin "3") (pinfunction "3_3") (pintype "passive"))
    )
    (net (code "51") (name "SL_3V3") (class "Default")
      (node (ref "J104") (pin "2") (pinfunction "2_2") (pintype "passive"))
      (node (ref "R108") (pin "2") (pinfunction "2_2") (pintype "passive"))
    )
    (net (code "52") (name "SL_GND") (class "Default")
      (node (ref "C111") (pin "1") (pinfunction "1_1") (pintype "passive"))
      (node (ref "J104") (pin "4") (pinfunction "4_4") (pintype "passive"))
      (node (ref "SW100") (pin "1") (pinfunction "1_1") (pintype "passive"))
      (node (ref "SW100") (pin "2") (pinfunction "2_2") (pintype "passive"))
      (node (ref "SW100") (pin "4") (pinfunction "4_4") (pintype "passive"))
      (node (ref "SW100") (pin "5") (pinfunction "5_5") (pintype "passive"))
    )
    (net (code "53") (name "SR_3V3") (class "Default")
      (node (ref "J105") (pin "2") (pinfunction "2_2") (pintype "passive"))
      (node (ref "R116") (pin "2") (pinfunction "2_2") (pintype "passive"))
    )
    (net (code "54") (name "SR_GND") (class "Default")
      (node (ref "C112") (pin "1") (pinfunction "1_1") (pintype "passive"))
      (node (ref "J105") (pin "4") (pinfunction "4_4") (pintype "passive"))
      (node (ref "SW102") (pin "1") (pinfunction "1_1") (pintype "passive"))
      (node (ref "SW102") (pin "2") (pinfunction "2_2") (pintype "passive"))
      (node (ref "SW102") (pin "4") (pinfunction "4_4") (pintype "passive"))
      (node (ref "SW102") (pin "5") (pinfunction "5_5") (pintype "passive"))
    )
    (net (code "55") (name "unconnected-(J100-SBU1-PadA8)") (class "Default")
      (node (ref "J100") (pin "A8") (pinfunction "SBU1_A8") (pintype "bidirectional+no_connect"))
    )
    (net (code "56") (name "unconnected-(J100-SBU2-PadB8)") (class "Default")
      (node (ref "J100") (pin "B8") (pinfunction "SBU2_B8") (pintype "bidirectional+no_connect"))
    )
    (net (code "57") (name "unconnected-(J101-Pad3)") (class "Default")
      (node (ref "J101") (pin "3") (pinfunction "3_3") (pintype "passive+no_connect"))
    )
    (net (code "58") (name "unconnected-(J102-Pad3)") (class "Default")
      (node (ref "J102") (pin "3") (pinfunction "3_3") (pintype "passive+no_connect"))
    )
    (net (code "59") (name "unconnected-(J104-Pad3)") (class "Default")
      (node (ref "J104") (pin "3") (pinfunction "3_3") (pintype "passive+no_connect"))
    )
    (net (code "60") (name "unconnected-(J105-Pad1)") (class "Default")
      (node (ref "J105") (pin "1") (pinfunction "1_1") (pintype "passive+no_connect"))
    )
    (net (code "61") (name "unconnected-(U100A-JNTRST-Pad40)") (class "Default")
      (node (ref "U100") (pin "40") (pinfunction "JNTRST_40") (pintype "bidirectional"))
    )
    (net (code "62") (name "unconnected-(U100A-JTCK_{slash}_SWCLK-Pad37)") (class "Default")
      (node (ref "U100") (pin "37") (pinfunction "JTCK_/_SWCLK_37") (pintype "bidirectional"))
    )
    (net (code "63") (name "unconnected-(U100A-JTDI-Pad38)") (class "Default")
      (node (ref "U100") (pin "38") (pinfunction "JTDI_38") (pintype "bidirectional"))
    )
    (net (code "64") (name "unconnected-(U100A-JTDO-Pad39)") (class "Default")
      (node (ref "U100") (pin "39") (pinfunction "JTDO_39") (pintype "bidirectional"))
    )
    (net (code "65") (name "unconnected-(U100A-JTMS_{slash}_SWDIO-Pad34)") (class "Default")
      (node (ref "U100") (pin "34") (pinfunction "JTMS_/_SWDIO_34") (pintype "bidirectional"))
    )
    (net (code "66") (name "unconnected-(U100A-PA4-Pad14)") (class "Default")
      (node (ref "U100") (pin "14") (pinfunction "PA4_14") (pintype "bidirectional"))
    )
    (net (code "67") (name "unconnected-(U100A-PA5-Pad15)") (class "Default")
      (node (ref "U100") (pin "15") (pinfunction "PA5_15") (pintype "bidirectional"))
    )
    (net (code "68") (name "unconnected-(U100A-PA6-Pad16)") (class "Default")
      (node (ref "U100") (pin "16") (pinfunction "PA6_16") (pintype "bidirectional"))
    )
    (net (code "69") (name "unconnected-(U100A-PA7-Pad17)") (class "Default")
      (node (ref "U100") (pin "17") (pinfunction "PA7_17") (pintype "bidirectional"))
    )
    (net (code "70") (name "unconnected-(U100A-PA8-Pad29)") (class "Default")
      (node (ref "U100") (pin "29") (pinfunction "PA8_29") (pintype "bidirectional"))
    )
    (net (code "71") (name "unconnected-(U100A-PB2_{slash}_BOOT1-Pad20)") (class "Default")
      (node (ref "U100") (pin "20") (pinfunction "PB2_/_BOOT1_20") (pintype "bidirectional"))
    )
    (net (code "72") (name "unconnected-(U100A-PB14-Pad27)") (class "Default")
      (node (ref "U100") (pin "27") (pinfunction "PB14_27") (pintype "bidirectional"))
    )
    (net (code "73") (name "unconnected-(U100A-PB15-Pad28)") (class "Default")
      (node (ref "U100") (pin "28") (pinfunction "PB15_28") (pintype "bidirectional"))
    )
    (net (code "74") (name "unconnected-(U100A-PC13-Pad2)") (class "Default")
      (node (ref "U100") (pin "2") (pinfunction "PC13_2") (pintype "bidirectional"))
    )
    (net (code "75") (name "unconnected-(U100A-PC14-Pad3)") (class "Default")
      (node (ref "U100") (pin "3") (pinfunction "PC14_3") (pintype "bidirectional"))
    )
    (net (code "76") (name "unconnected-(U100A-PC15-Pad4)") (class "Default")
      (node (ref "U100") (pin "4") (pinfunction "PC15_4") (pintype "bidirectional"))
    )
  )
)
